# US_EPS_RS485.net
KiCad netlist of a schematic drawn in Altium Designer
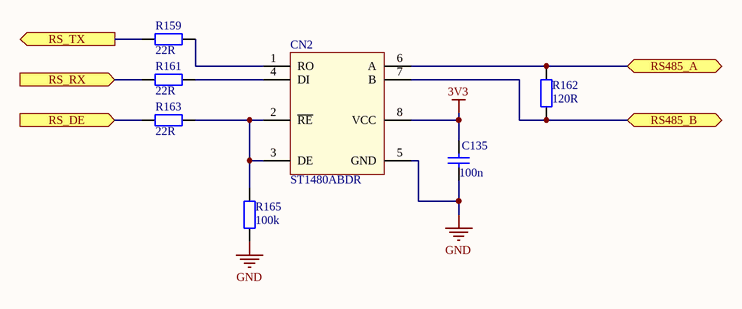
[diagram p0: US_EPS_RS485.SchDoc]

(export (version "E")
  (design (tool "Eeschema 10.0.6"))
  (components
    (comp (ref "C135")
      (value "100n")
      (footprint "C0603_IPC_HD")
      (description "CAP CER 0.1UF 16V X7R 0603")
      (fields
        (field (name "MANUFACTURER") "Samsung Electro-Mechanics")
        (field (name "MANUFACTURER PART NUMBER") "CL10B104KO8NNNC")
      )
      (libsource (lib "alfasat_lib") (part "CL10B104KO8NNNC"))
    )
    (comp (ref "CN2")
      (value "ST1480ABDR")
      (footprint "SOIC-8")
      (description "IC TXRX 3.3V RS485/422 8 SOIC")
      (fields (field (name "MANUFACTURER") "STMicroelectronics"))
      (libsource (lib "alfasat_parts_lib") (part "ST1480ABDR"))
    )
    (comp (ref "R159")
      (value "22R")
      (footprint "R0603_IPC_MD")
      (description "RES SMD 22 OHM 5% 1/10W 0603")
      (fields
        (field (name "MANUFACTURER") "Bourns Inc.")
        (field (name "MANUFACTURER PART NUMBER") "CR0603-JW-220ELF")
      )
      (libsource (lib "alfasat_lib") (part "CR0603-JW-220ELF"))
    )
    (comp (ref "R161")
      (value "22R")
      (footprint "R0603_IPC_MD")
      (description "RES SMD 22 OHM 5% 1/10W 0603")
      (fields
        (field (name "MANUFACTURER") "Bourns Inc.")
        (field (name "MANUFACTURER PART NUMBER") "CR0603-JW-220ELF")
      )
      (libsource (lib "alfasat_lib") (part "CR0603-JW-220ELF"))
    )
    (comp (ref "R162")
      (value "120R")
      (footprint "C0603_IPC_MD")
      (description "RES SMD 120 OHM 5% 1/10W 0603")
      (fields
        (field (name "MANUFACTURER") "Yageo")
        (field (name "MANUFACTURER PART NUMBER") "RC0603JR-07120RL")
      )
      (libsource (lib "alfasat_lib") (part "RC0603JR-07120RL"))
    )
    (comp (ref "R163")
      (value "22R")
      (footprint "R0603_IPC_MD")
      (description "RES SMD 22 OHM 5% 1/10W 0603")
      (fields
        (field (name "MANUFACTURER") "Bourns Inc.")
        (field (name "MANUFACTURER PART NUMBER") "CR0603-JW-220ELF")
      )
      (libsource (lib "alfasat_lib") (part "CR0603-JW-220ELF"))
    )
    (comp (ref "R165")
      (value "100k")
      (footprint "R0603_IPC_MD")
      (description "RES 100K OHM 1% 1/10W 0603")
      (fields
        (field (name "MANUFACTURER") "Stackpole Electronics Inc")
        (field (name "MANUFACTURER PART NUMBER") "RMCF0603FT100K")
      )
      (libsource (lib "alfasat_lib_eps") (part "CR0603-JW-104ELF"))
    )
  )
  (nets
    (net (code "1") (name "/RS485_A") (class "Default")
      (node (ref "CN2") (pin "6") (pinfunction "A_6") (pintype "passive"))
      (node (ref "R162") (pin "2") (pinfunction "2_2") (pintype "passive"))
    )
    (net (code "2") (name "/RS485_B") (class "Default")
      (node (ref "CN2") (pin "7") (pinfunction "B_7") (pintype "passive"))
      (node (ref "R162") (pin "1") (pinfunction "1_1") (pintype "passive"))
    )
    (net (code "3") (name "/RS_DE") (class "Default")
      (node (ref "R163") (pin "1") (pinfunction "1_1") (pintype "passive"))
    )
    (net (code "4") (name "/RS_RX") (class "Default")
      (node (ref "R161") (pin "1") (pinfunction "1_1") (pintype "passive"))
    )
    (net (code "5") (name "/RS_TX") (class "Default")
      (node (ref "R159") (pin "1") (pinfunction "1_1") (pintype "passive"))
    )
    (net (code "6") (name "3V3") (class "Default")
      (node (ref "C135") (pin "2") (pinfunction "2_2") (pintype "passive"))
      (node (ref "CN2") (pin "8") (pinfunction "VCC_8") (pintype "passive"))
    )
    (net (code "7") (name "GND") (class "Default")
      (node (ref "C135") (pin "1") (pinfunction "1_1") (pintype "passive"))
      (node (ref "CN2") (pin "5") (pinfunction "GND_5") (pintype "passive"))
      (node (ref "R165") (pin "1") (pinfunction "1_1") (pintype "passive"))
    )
    (net (code "8") (name "Net-(CN2-DE)") (class "Default")
      (node (ref "CN2") (pin "2") (pinfunction "~{RE}_2") (pintype "passive"))
      (node (ref "CN2") (pin "3") (pinfunction "DE_3") (pintype "passive"))
      (node (ref "R163") (pin "2") (pinfunction "2_2") (pintype "passive"))
      (node (ref "R165") (pin "2") (pinfunction "2_2") (pintype "passive"))
    )
    (net (code "9") (name "Net-(CN2-DI)") (class "Default")
      (node (ref "CN2") (pin "4") (pinfunction "DI_4") (pintype "passive"))
      (node (ref "R161") (pin "2") (pinfunction "2_2") (pintype "passive"))
    )
    (net (code "10") (name "Net-(CN2-RO)") (class "Default")
      (node (ref "CN2") (pin "1") (pinfunction "RO_1") (pintype "passive"))
      (node (ref "R159") (pin "2") (pinfunction "2_2") (pintype "passive"))
    )
  )
)
